# PIC18_DEV_BOARD.net
KiCad netlist of a schematic drawn in EAGLE
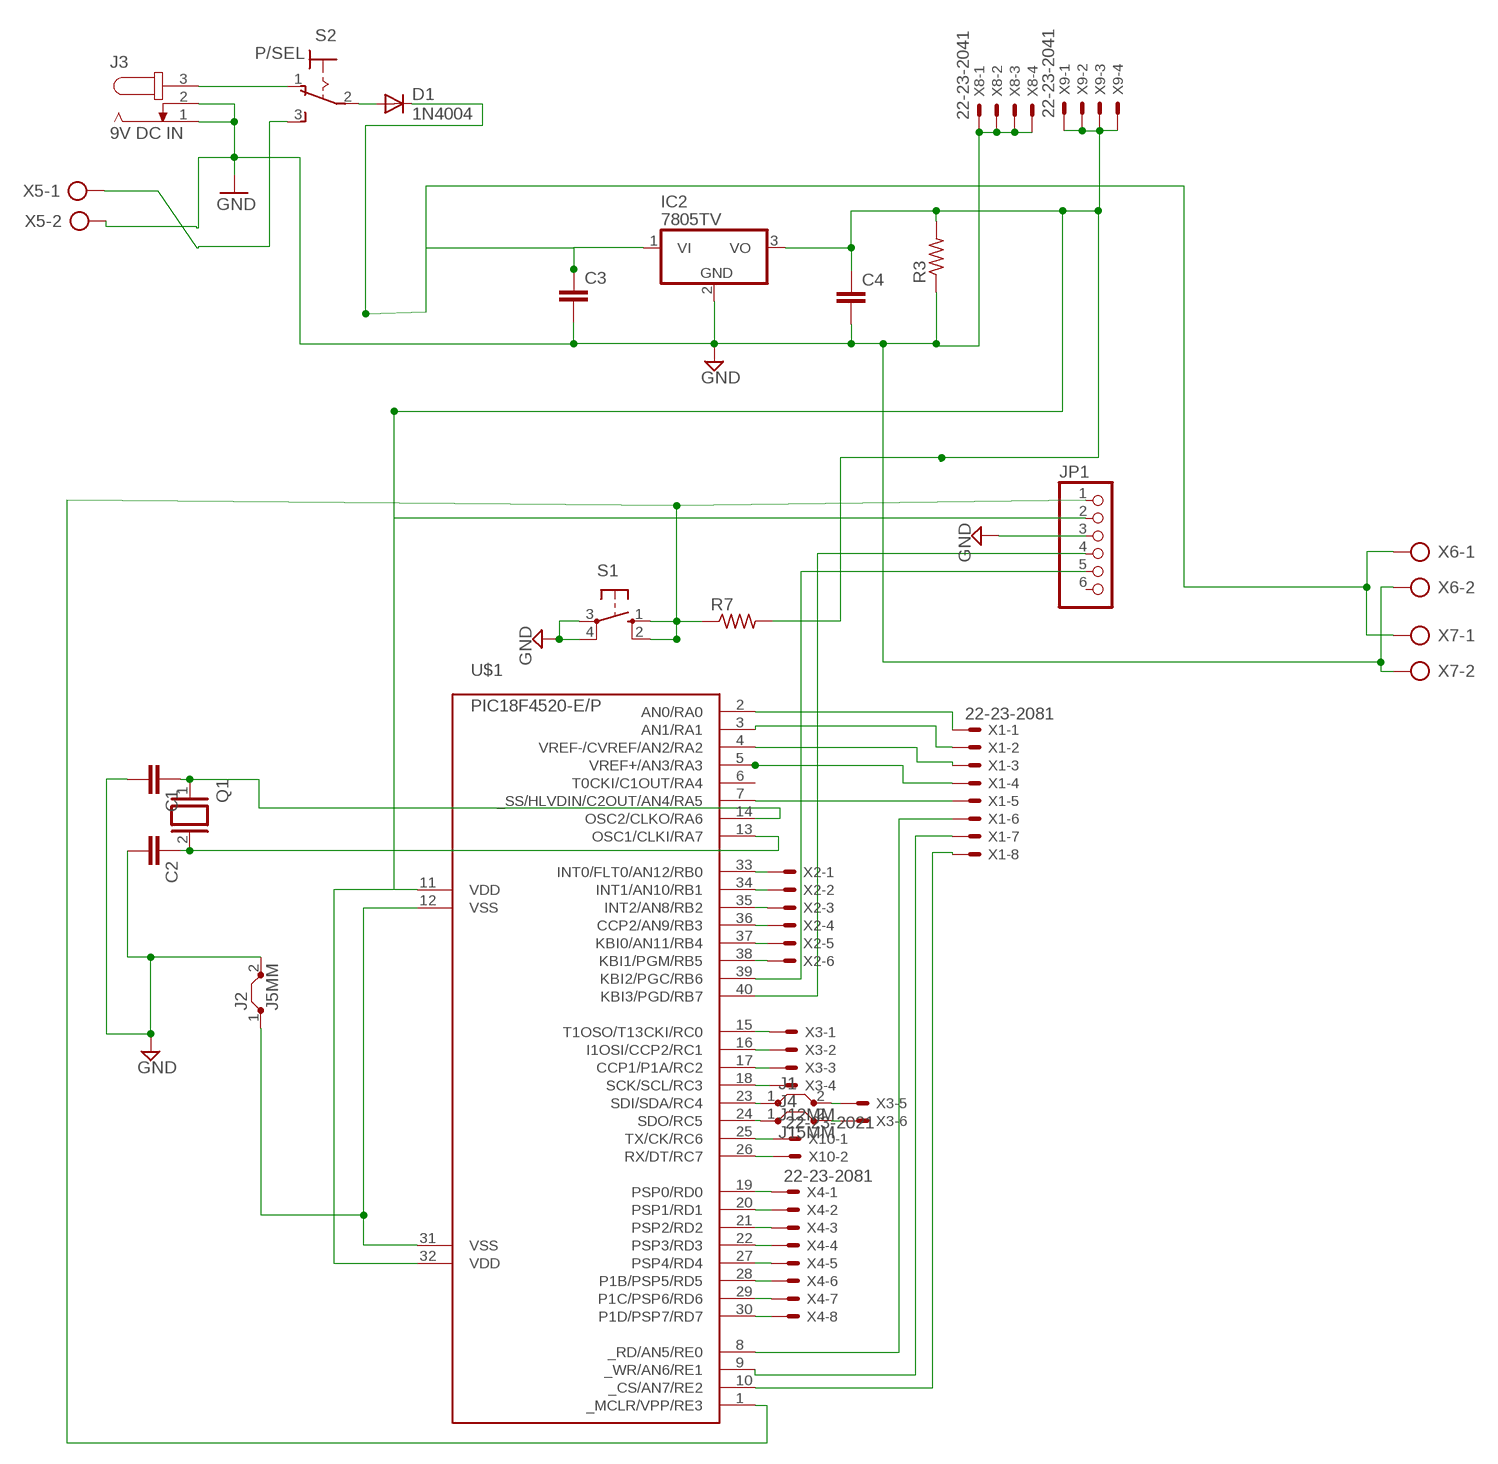
[diagram p0: schematic, sheet 1]

(export (version "E")
  (design (tool "Eeschema 10.0.6"))
  (components
    (comp (ref "C1")
      (value "C-EU025-025X050")
      (footprint "eagle-import:C025-025X050")
      (libsource (lib "eagle-import") (part "C-EU025-025X050"))
    )
    (comp (ref "C2")
      (value "C-EU025-025X050")
      (footprint "eagle-import:C025-025X050")
      (libsource (lib "eagle-import") (part "C-EU025-025X050"))
    )
    (comp (ref "C3")
      (value "C-EU025-025X050")
      (footprint "eagle-import:C025-025X050")
      (libsource (lib "eagle-import") (part "C-EU025-025X050"))
    )
    (comp (ref "C4")
      (value "C-EU025-025X050")
      (footprint "eagle-import:C025-025X050")
      (libsource (lib "eagle-import") (part "C-EU025-025X050"))
    )
    (comp (ref "D1")
      (value "1N4004")
      (footprint "eagle-import:DO41-10")
      (fields (field (name "MF") "MULTICOMP"))
      (libsource (lib "eagle-import") (part "1N4004"))
    )
    (comp (ref "IC2")
      (value "7805TV")
      (footprint "eagle-import:TO220V")
      (libsource (lib "eagle-import") (part "78TV05"))
    )
    (comp (ref "J1")
      (value "J12MM")
      (footprint "eagle-import:12")
      (libsource (lib "eagle-import") (part "J12MM"))
    )
    (comp (ref "J2")
      (value "J5MM")
      (footprint "eagle-import:05")
      (libsource (lib "eagle-import") (part "J5MM"))
    )
    (comp (ref "J3")
      (value "9V DC IN")
      (footprint "eagle-import:SPC4077")
      (fields
        (field (name "MF") "SWITCHCRAFT")
        (field (name "MPN") "RAPC722X")
        (field (name "OC_FARNELL") "1608727")
      )
      (libsource (lib "eagle-import") (part "JACK-PLUG0"))
    )
    (comp (ref "J4")
      (value "J15MM")
      (footprint "eagle-import:15")
      (libsource (lib "eagle-import") (part "J15MM"))
    )
    (comp (ref "JP1")
      (value "PINHD-1X6")
      (footprint "eagle-import:1X06")
      (libsource (lib "eagle-import") (part "PINHD-1X6"))
    )
    (comp (ref "Q1")
      (value "XTAL/S")
      (footprint "eagle-import:QS")
      (libsource (lib "eagle-import") (part "XTAL/S"))
    )
    (comp (ref "R3")
      (value "R-US_0207/10")
      (footprint "eagle-import:0207_10")
      (libsource (lib "eagle-import") (part "R-US_0207/10"))
    )
    (comp (ref "R7")
      (value "R-US_0207/10")
      (footprint "eagle-import:0207_10")
      (libsource (lib "eagle-import") (part "R-US_0207/10"))
    )
    (comp (ref "S1")
      (value "10-XX")
      (footprint "eagle-import:B3F-10XX")
      (fields (field (name "MPN") "B3F-1000"))
      (libsource (lib "eagle-import") (part "10-XX"))
    )
    (comp (ref "S2")
      (value "P/SEL")
      (footprint "eagle-import:320-916")
      (fields (field (name "MF") "APEM") (field (name "MPN") "5636A9"))
      (libsource (lib "eagle-import") (part "320-916"))
    )
    (comp (ref "U$1")
      (value "PIC18F4520-E/P")
      (footprint "eagle-import:DIL40")
      (libsource (lib "eagle-import") (part "PIC184520-E/PF"))
    )
    (comp (ref "X1")
      (value "22-23-2081")
      (footprint "eagle-import:22-23-2081")
      (fields (field (name "MF") "MOLEX"))
      (libsource (lib "eagle-import") (part "22-23-2081"))
    )
    (comp (ref "X2")
      (value "22-23-2061")
      (footprint "eagle-import:22-23-2061")
      (fields (field (name "MF") "MOLEX"))
      (libsource (lib "eagle-import") (part "22-23-2061"))
    )
    (comp (ref "X3")
      (value "22-23-2061")
      (footprint "eagle-import:22-23-2061")
      (fields (field (name "MF") "MOLEX"))
      (libsource (lib "eagle-import") (part "22-23-2061"))
    )
    (comp (ref "X4")
      (value "22-23-2081")
      (footprint "eagle-import:22-23-2081")
      (fields (field (name "MF") "MOLEX"))
      (libsource (lib "eagle-import") (part "22-23-2081"))
    )
    (comp (ref "X5")
      (value "AK500/2-H")
      (footprint "eagle-import:AK500_2-H")
      (libsource (lib "eagle-import") (part "AK500/2-H"))
    )
    (comp (ref "X6")
      (value "AK500/2-H")
      (footprint "eagle-import:AK500_2-H")
      (libsource (lib "eagle-import") (part "AK500/2-H"))
    )
    (comp (ref "X7")
      (value "AK500/2-H")
      (footprint "eagle-import:AK500_2-H")
      (libsource (lib "eagle-import") (part "AK500/2-H"))
    )
    (comp (ref "X8")
      (value "22-23-2041")
      (footprint "eagle-import:22-23-2041")
      (fields (field (name "MF") "MOLEX"))
      (libsource (lib "eagle-import") (part "22-23-2041"))
    )
    (comp (ref "X9")
      (value "22-23-2041")
      (footprint "eagle-import:22-23-2041")
      (fields (field (name "MF") "MOLEX"))
      (libsource (lib "eagle-import") (part "22-23-2041"))
    )
    (comp (ref "X10")
      (value "22-23-2021")
      (footprint "eagle-import:22-23-2021")
      (fields (field (name "MF") "MOLEX"))
      (libsource (lib "eagle-import") (part "22-23-2021"))
    )
  )
  (nets
    (net (code "1") (name "GND") (class "Default")
      (node (ref "C1") (pin "2") (pinfunction "2_2") (pintype "passive"))
      (node (ref "C2") (pin "2") (pinfunction "2_2") (pintype "passive"))
      (node (ref "C3") (pin "2") (pinfunction "2_2") (pintype "passive"))
      (node (ref "C4") (pin "2") (pinfunction "2_2") (pintype "passive"))
      (node (ref "IC2") (pin "2") (pinfunction "GND_2") (pintype "passive"))
      (node (ref "J2") (pin "2") (pinfunction "2_2") (pintype "passive"))
      (node (ref "J3") (pin "1") (pinfunction "1_1") (pintype "passive"))
      (node (ref "J3") (pin "2") (pinfunction "2_2") (pintype "passive"))
      (node (ref "JP1") (pin "3") (pinfunction "3_3") (pintype "passive"))
      (node (ref "R3") (pin "1") (pinfunction "1_1") (pintype "passive"))
      (node (ref "S1") (pin "3") (pinfunction "P_3") (pintype "passive"))
      (node (ref "S1") (pin "4") (pinfunction "P1_4") (pintype "passive"))
      (node (ref "X5") (pin "2") (pinfunction "KL_2") (pintype "passive"))
      (node (ref "X6") (pin "2") (pinfunction "KL_2") (pintype "passive"))
      (node (ref "X7") (pin "2") (pinfunction "KL_2") (pintype "passive"))
      (node (ref "X8") (pin "1") (pinfunction "S_1") (pintype "passive"))
      (node (ref "X8") (pin "2") (pinfunction "S_2") (pintype "passive"))
      (node (ref "X8") (pin "3") (pinfunction "S_3") (pintype "passive"))
      (node (ref "X8") (pin "4") (pinfunction "S_4") (pintype "passive"))
    )
    (net (code "2") (name "Net-(IC2-VI)") (class "Default")
      (node (ref "C3") (pin "1") (pinfunction "1_1") (pintype "passive"))
      (node (ref "D1") (pin "C") (pinfunction "C_C") (pintype "passive"))
      (node (ref "IC2") (pin "1") (pinfunction "VI_1") (pintype "input"))
      (node (ref "X6") (pin "1") (pinfunction "KL_1") (pintype "passive"))
      (node (ref "X7") (pin "1") (pinfunction "KL_1") (pintype "passive"))
    )
    (net (code "3") (name "Net-(IC2-VO)") (class "Default")
      (node (ref "C4") (pin "1") (pinfunction "1_1") (pintype "passive"))
      (node (ref "IC2") (pin "3") (pinfunction "VO_3") (pintype "passive"))
      (node (ref "JP1") (pin "2") (pinfunction "2_2") (pintype "passive"))
      (node (ref "R3") (pin "2") (pinfunction "2_2") (pintype "passive"))
      (node (ref "R7") (pin "2") (pinfunction "2_2") (pintype "passive"))
      (node (ref "U$1") (pin "11") (pinfunction "VDD_11") (pintype "power_in"))
      (node (ref "U$1") (pin "32") (pinfunction "VDD_32") (pintype "power_in"))
      (node (ref "X9") (pin "1") (pinfunction "S_1") (pintype "passive"))
      (node (ref "X9") (pin "2") (pinfunction "S_2") (pintype "passive"))
      (node (ref "X9") (pin "3") (pinfunction "S_3") (pintype "passive"))
      (node (ref "X9") (pin "4") (pinfunction "S_4") (pintype "passive"))
    )
    (net (code "4") (name "Net-(J2-Pad1)") (class "Default")
      (node (ref "J2") (pin "1") (pinfunction "1_1") (pintype "passive"))
      (node (ref "U$1") (pin "12") (pinfunction "VSS_12") (pintype "power_in"))
      (node (ref "U$1") (pin "31") (pinfunction "VSS_31") (pintype "power_in"))
    )
    (net (code "5") (name "Net-(S1-S)") (class "Default")
      (node (ref "JP1") (pin "1") (pinfunction "1_1") (pintype "passive"))
      (node (ref "R7") (pin "1") (pinfunction "1_1") (pintype "passive"))
      (node (ref "S1") (pin "1") (pinfunction "S_1") (pintype "passive"))
      (node (ref "S1") (pin "2") (pinfunction "S1_2") (pintype "passive"))
      (node (ref "U$1") (pin "1") (pinfunction "_MCLR/VPP/RE3_1") (pintype "input"))
    )
    (net (code "6") (name "Net-(S2-O)") (class "Default")
      (node (ref "J3") (pin "3") (pinfunction "3_3") (pintype "passive"))
      (node (ref "S2") (pin "1") (pinfunction "O_1") (pintype "passive"))
    )
    (net (code "7") (name "Net-(S2-P)") (class "Default")
      (node (ref "D1") (pin "A") (pinfunction "A_A") (pintype "passive"))
      (node (ref "S2") (pin "2") (pinfunction "P_2") (pintype "passive"))
    )
    (net (code "8") (name "Net-(S2-S)") (class "Default")
      (node (ref "S2") (pin "3") (pinfunction "S_3") (pintype "passive"))
      (node (ref "X5") (pin "1") (pinfunction "KL_1") (pintype "passive"))
    )
    (net (code "9") (name "Net-(U$1-AN0{slash}RA0)") (class "Default")
      (node (ref "U$1") (pin "2") (pinfunction "AN0/RA0_2") (pintype "bidirectional"))
      (node (ref "X1") (pin "1") (pinfunction "S_1") (pintype "passive"))
    )
    (net (code "10") (name "Net-(U$1-AN1{slash}RA1)") (class "Default")
      (node (ref "U$1") (pin "3") (pinfunction "AN1/RA1_3") (pintype "bidirectional"))
      (node (ref "X1") (pin "2") (pinfunction "S_2") (pintype "passive"))
    )
    (net (code "11") (name "Net-(U$1-CCP1{slash}P1A{slash}RC2)") (class "Default")
      (node (ref "U$1") (pin "17") (pinfunction "CCP1/P1A/RC2_17") (pintype "bidirectional"))
      (node (ref "X3") (pin "3") (pinfunction "S_3") (pintype "passive"))
    )
    (net (code "12") (name "Net-(U$1-CCP2{slash}AN9{slash}RB3)") (class "Default")
      (node (ref "U$1") (pin "36") (pinfunction "CCP2/AN9/RB3_36") (pintype "bidirectional"))
      (node (ref "X2") (pin "4") (pinfunction "S_4") (pintype "passive"))
    )
    (net (code "13") (name "Net-(U$1-I1OSI{slash}CCP2{slash}RC1)") (class "Default")
      (node (ref "U$1") (pin "16") (pinfunction "I1OSI/CCP2/RC1_16") (pintype "bidirectional"))
      (node (ref "X3") (pin "2") (pinfunction "S_2") (pintype "passive"))
    )
    (net (code "14") (name "Net-(U$1-INT0{slash}FLT0{slash}AN12{slash}RB0)") (class "Default")
      (node (ref "U$1") (pin "33") (pinfunction "INT0/FLT0/AN12/RB0_33") (pintype "bidirectional"))
      (node (ref "X2") (pin "1") (pinfunction "S_1") (pintype "passive"))
    )
    (net (code "15") (name "Net-(U$1-INT1{slash}AN10{slash}RB1)") (class "Default")
      (node (ref "U$1") (pin "34") (pinfunction "INT1/AN10/RB1_34") (pintype "bidirectional"))
      (node (ref "X2") (pin "2") (pinfunction "S_2") (pintype "passive"))
    )
    (net (code "16") (name "Net-(U$1-INT2{slash}AN8{slash}RB2)") (class "Default")
      (node (ref "U$1") (pin "35") (pinfunction "INT2/AN8/RB2_35") (pintype "bidirectional"))
      (node (ref "X2") (pin "3") (pinfunction "S_3") (pintype "passive"))
    )
    (net (code "17") (name "Net-(U$1-KBI0{slash}AN11{slash}RB4)") (class "Default")
      (node (ref "U$1") (pin "37") (pinfunction "KBI0/AN11/RB4_37") (pintype "bidirectional"))
      (node (ref "X2") (pin "5") (pinfunction "S_5") (pintype "passive"))
    )
    (net (code "18") (name "Net-(U$1-KBI1{slash}PGM{slash}RB5)") (class "Default")
      (node (ref "U$1") (pin "38") (pinfunction "KBI1/PGM/RB5_38") (pintype "bidirectional"))
      (node (ref "X2") (pin "6") (pinfunction "S_6") (pintype "passive"))
    )
    (net (code "19") (name "Net-(U$1-KBI2{slash}PGC{slash}RB6)") (class "Default")
      (node (ref "JP1") (pin "5") (pinfunction "5_5") (pintype "passive"))
      (node (ref "U$1") (pin "39") (pinfunction "KBI2/PGC/RB6_39") (pintype "bidirectional"))
    )
    (net (code "20") (name "Net-(U$1-KBI3{slash}PGD{slash}RB7)") (class "Default")
      (node (ref "JP1") (pin "4") (pinfunction "4_4") (pintype "passive"))
      (node (ref "U$1") (pin "40") (pinfunction "KBI3/PGD/RB7_40") (pintype "bidirectional"))
    )
    (net (code "21") (name "Net-(U$1-OSC1{slash}CLKI{slash}RA7)") (class "Default")
      (node (ref "C2") (pin "1") (pinfunction "1_1") (pintype "passive"))
      (node (ref "Q1") (pin "2") (pinfunction "2_2") (pintype "passive"))
      (node (ref "U$1") (pin "13") (pinfunction "OSC1/CLKI/RA7_13") (pintype "bidirectional"))
    )
    (net (code "22") (name "Net-(U$1-OSC2{slash}CLKO{slash}RA6)") (class "Default")
      (node (ref "C1") (pin "1") (pinfunction "1_1") (pintype "passive"))
      (node (ref "Q1") (pin "1") (pinfunction "1_1") (pintype "passive"))
      (node (ref "U$1") (pin "14") (pinfunction "OSC2/CLKO/RA6_14") (pintype "bidirectional"))
    )
    (net (code "23") (name "Net-(U$1-P1B{slash}PSP5{slash}RD5)") (class "Default")
      (node (ref "U$1") (pin "28") (pinfunction "P1B/PSP5/RD5_28") (pintype "bidirectional"))
      (node (ref "X4") (pin "6") (pinfunction "S_6") (pintype "passive"))
    )
    (net (code "24") (name "Net-(U$1-P1C{slash}PSP6{slash}RD6)") (class "Default")
      (node (ref "U$1") (pin "29") (pinfunction "P1C/PSP6/RD6_29") (pintype "bidirectional"))
      (node (ref "X4") (pin "7") (pinfunction "S_7") (pintype "passive"))
    )
    (net (code "25") (name "Net-(U$1-P1D{slash}PSP7{slash}RD7)") (class "Default")
      (node (ref "U$1") (pin "30") (pinfunction "P1D/PSP7/RD7_30") (pintype "bidirectional"))
      (node (ref "X4") (pin "8") (pinfunction "S_8") (pintype "passive"))
    )
    (net (code "26") (name "Net-(U$1-PSP0{slash}RD0)") (class "Default")
      (node (ref "U$1") (pin "19") (pinfunction "PSP0/RD0_19") (pintype "bidirectional"))
      (node (ref "X4") (pin "1") (pinfunction "S_1") (pintype "passive"))
    )
    (net (code "27") (name "Net-(U$1-PSP1{slash}RD1)") (class "Default")
      (node (ref "U$1") (pin "20") (pinfunction "PSP1/RD1_20") (pintype "bidirectional"))
      (node (ref "X4") (pin "2") (pinfunction "S_2") (pintype "passive"))
    )
    (net (code "28") (name "Net-(U$1-PSP2{slash}RD2)") (class "Default")
      (node (ref "U$1") (pin "21") (pinfunction "PSP2/RD2_21") (pintype "bidirectional"))
      (node (ref "X4") (pin "3") (pinfunction "S_3") (pintype "passive"))
    )
    (net (code "29") (name "Net-(U$1-PSP3{slash}RD3)") (class "Default")
      (node (ref "U$1") (pin "22") (pinfunction "PSP3/RD3_22") (pintype "bidirectional"))
      (node (ref "X4") (pin "4") (pinfunction "S_4") (pintype "passive"))
    )
    (net (code "30") (name "Net-(U$1-PSP4{slash}RD4)") (class "Default")
      (node (ref "U$1") (pin "27") (pinfunction "PSP4/RD4_27") (pintype "bidirectional"))
      (node (ref "X4") (pin "5") (pinfunction "S_5") (pintype "passive"))
    )
    (net (code "31") (name "Net-(U$1-RX{slash}DT{slash}RC7)") (class "Default")
      (node (ref "U$1") (pin "26") (pinfunction "RX/DT/RC7_26") (pintype "bidirectional"))
      (node (ref "X10") (pin "2") (pinfunction "S_2") (pintype "passive"))
    )
    (net (code "32") (name "Net-(U$1-SCK{slash}SCL{slash}RC3)") (class "Default")
      (node (ref "U$1") (pin "18") (pinfunction "SCK/SCL/RC3_18") (pintype "bidirectional"))
      (node (ref "X3") (pin "4") (pinfunction "S_4") (pintype "passive"))
    )
    (net (code "33") (name "Net-(U$1-SDI{slash}SDA{slash}RC4)") (class "Default")
      (node (ref "J1") (pin "1") (pinfunction "1_1") (pintype "passive"))
      (node (ref "U$1") (pin "23") (pinfunction "SDI/SDA/RC4_23") (pintype "bidirectional"))
    )
    (net (code "34") (name "Net-(U$1-SDO{slash}RC5)") (class "Default")
      (node (ref "J4") (pin "1") (pinfunction "1_1") (pintype "passive"))
      (node (ref "U$1") (pin "24") (pinfunction "SDO/RC5_24") (pintype "bidirectional"))
    )
    (net (code "35") (name "Net-(U$1-T1OSO{slash}T13CKI{slash}RC0)") (class "Default")
      (node (ref "U$1") (pin "15") (pinfunction "T1OSO/T13CKI/RC0_15") (pintype "bidirectional"))
      (node (ref "X3") (pin "1") (pinfunction "S_1") (pintype "passive"))
    )
    (net (code "36") (name "Net-(U$1-TX{slash}CK{slash}RC6)") (class "Default")
      (node (ref "U$1") (pin "25") (pinfunction "TX/CK/RC6_25") (pintype "bidirectional"))
      (node (ref "X10") (pin "1") (pinfunction "S_1") (pintype "passive"))
    )
    (net (code "37") (name "Net-(U$1-VREF+{slash}AN3{slash}RA3)") (class "Default")
      (node (ref "U$1") (pin "5") (pinfunction "VREF+/AN3/RA3_5") (pintype "bidirectional"))
      (node (ref "X1") (pin "4") (pinfunction "S_4") (pintype "passive"))
    )
    (net (code "38") (name "Net-(U$1-VREF-{slash}CVREF{slash}AN2{slash}RA2)") (class "Default")
      (node (ref "U$1") (pin "4") (pinfunction "VREF-/CVREF/AN2/RA2_4") (pintype "bidirectional"))
      (node (ref "X1") (pin "3") (pinfunction "S_3") (pintype "passive"))
    )
    (net (code "39") (name "Net-(U$1-_CS{slash}AN7{slash}RE2)") (class "Default")
      (node (ref "U$1") (pin "10") (pinfunction "_CS/AN7/RE2_10") (pintype "bidirectional"))
      (node (ref "X1") (pin "8") (pinfunction "S_8") (pintype "passive"))
    )
    (net (code "40") (name "Net-(U$1-_RD{slash}AN5{slash}RE0)") (class "Default")
      (node (ref "U$1") (pin "8") (pinfunction "_RD/AN5/RE0_8") (pintype "bidirectional"))
      (node (ref "X1") (pin "6") (pinfunction "S_6") (pintype "passive"))
    )
    (net (code "41") (name "Net-(U$1-_SS{slash}HLVDIN{slash}C2OUT{slash}AN4{slash}RA5)") (class "Default")
      (node (ref "U$1") (pin "7") (pinfunction "_SS/HLVDIN/C2OUT/AN4/RA5_7") (pintype "bidirectional"))
      (node (ref "X1") (pin "5") (pinfunction "S_5") (pintype "passive"))
    )
    (net (code "42") (name "Net-(U$1-_WR{slash}AN6{slash}RE1)") (class "Default")
      (node (ref "U$1") (pin "9") (pinfunction "_WR/AN6/RE1_9") (pintype "bidirectional"))
      (node (ref "X1") (pin "7") (pinfunction "S_7") (pintype "passive"))
    )
    (net (code "43") (name "Net-(X3E-S)") (class "Default")
      (node (ref "J1") (pin "2") (pinfunction "2_2") (pintype "passive"))
      (node (ref "X3") (pin "5") (pinfunction "S_5") (pintype "passive"))
    )
    (net (code "44") (name "Net-(X3F-S)") (class "Default")
      (node (ref "J4") (pin "2") (pinfunction "2_2") (pintype "passive"))
      (node (ref "X3") (pin "6") (pinfunction "S_6") (pintype "passive"))
    )
    (net (code "45") (name "unconnected-(JP1-Pad6)") (class "Default")
      (node (ref "JP1") (pin "6") (pinfunction "6_6") (pintype "passive"))
    )
    (net (code "46") (name "unconnected-(U$1-T0CKI{slash}C1OUT{slash}RA4-Pad6)") (class "Default")
      (node (ref "U$1") (pin "6") (pinfunction "T0CKI/C1OUT/RA4_6") (pintype "bidirectional"))
    )
  )
)
